# pureModExample.net
KiCad netlist of a schematic drawn in EAGLE
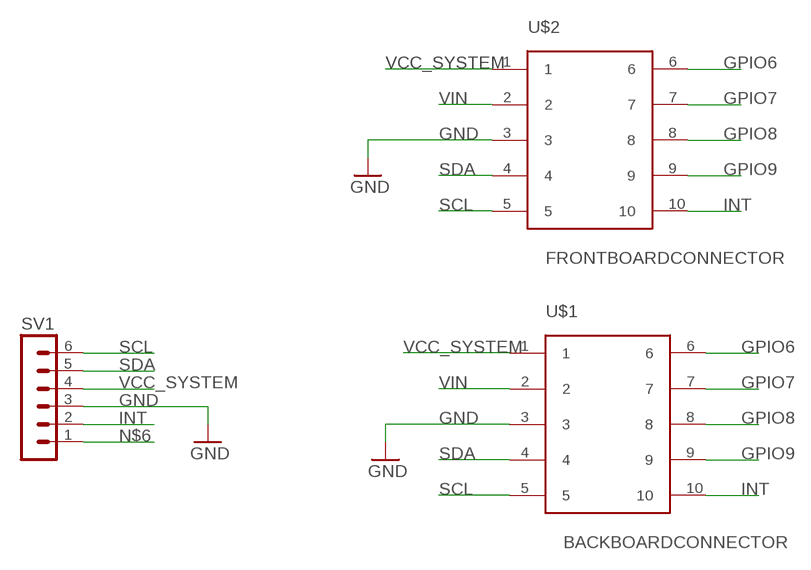
[diagram p0: schematic, sheet 1]

(export (version "E")
  (design (tool "Eeschema 10.0.6"))
  (components
    (comp (ref "SV1")
      (value "MA06-1")
      (footprint "eagle-import:MA06-1")
      (libsource (lib "eagle-import") (part "MA06-1"))
    )
    (comp (ref "U$1")
      (value "BACKBOARDCONNECTOR")
      (footprint "eagle-import:BACKBOARDCONNECTOR")
      (libsource (lib "eagle-import") (part "BACKBOARDCONNECTOR"))
    )
    (comp (ref "U$2")
      (value "FRONTBOARDCONNECTOR")
      (footprint "eagle-import:FRONTBOARDCONNECTOR")
      (libsource (lib "eagle-import") (part "FRONTBOARDCONNECTOR"))
    )
  )
  (nets
    (net (code "1") (name "/GPIO6") (class "Default")
      (node (ref "U$1") (pin "6") (pinfunction "6_6") (pintype "bidirectional"))
      (node (ref "U$2") (pin "6") (pinfunction "6_6") (pintype "bidirectional"))
    )
    (net (code "2") (name "/GPIO7") (class "Default")
      (node (ref "U$1") (pin "7") (pinfunction "7_7") (pintype "bidirectional"))
      (node (ref "U$2") (pin "7") (pinfunction "7_7") (pintype "bidirectional"))
    )
    (net (code "3") (name "/GPIO8") (class "Default")
      (node (ref "U$1") (pin "8") (pinfunction "8_8") (pintype "bidirectional"))
      (node (ref "U$2") (pin "8") (pinfunction "8_8") (pintype "bidirectional"))
    )
    (net (code "4") (name "/GPIO9") (class "Default")
      (node (ref "U$1") (pin "9") (pinfunction "9_9") (pintype "bidirectional"))
      (node (ref "U$2") (pin "9") (pinfunction "9_9") (pintype "bidirectional"))
    )
    (net (code "5") (name "/INT") (class "Default")
      (node (ref "SV1") (pin "2") (pinfunction "2_2") (pintype "passive"))
      (node (ref "U$1") (pin "10") (pinfunction "10_10") (pintype "bidirectional"))
      (node (ref "U$2") (pin "10") (pinfunction "10_10") (pintype "bidirectional"))
    )
    (net (code "6") (name "/N$6") (class "Default")
      (node (ref "SV1") (pin "1") (pinfunction "1_1") (pintype "passive"))
    )
    (net (code "7") (name "/SCL") (class "Default")
      (node (ref "SV1") (pin "6") (pinfunction "6_6") (pintype "passive"))
      (node (ref "U$1") (pin "5") (pinfunction "5_5") (pintype "bidirectional"))
      (node (ref "U$2") (pin "5") (pinfunction "5_5") (pintype "bidirectional"))
    )
    (net (code "8") (name "/SDA") (class "Default")
      (node (ref "SV1") (pin "5") (pinfunction "5_5") (pintype "passive"))
      (node (ref "U$1") (pin "4") (pinfunction "4_4") (pintype "bidirectional"))
      (node (ref "U$2") (pin "4") (pinfunction "4_4") (pintype "bidirectional"))
    )
    (net (code "9") (name "/VCC_SYSTEM") (class "Default")
      (node (ref "SV1") (pin "4") (pinfunction "4_4") (pintype "passive"))
      (node (ref "U$1") (pin "1") (pinfunction "1_1") (pintype "bidirectional"))
      (node (ref "U$2") (pin "1") (pinfunction "1_1") (pintype "bidirectional"))
    )
    (net (code "10") (name "/VIN") (class "Default")
      (node (ref "U$1") (pin "2") (pinfunction "2_2") (pintype "bidirectional"))
      (node (ref "U$2") (pin "2") (pinfunction "2_2") (pintype "bidirectional"))
    )
    (net (code "11") (name "GND") (class "Default")
      (node (ref "SV1") (pin "3") (pinfunction "3_3") (pintype "passive"))
      (node (ref "U$1") (pin "3") (pinfunction "3_3") (pintype "bidirectional"))
      (node (ref "U$2") (pin "3") (pinfunction "3_3") (pintype "bidirectional"))
    )
  )
)
